# apo_board.net
KiCad netlist of a schematic drawn in EAGLE
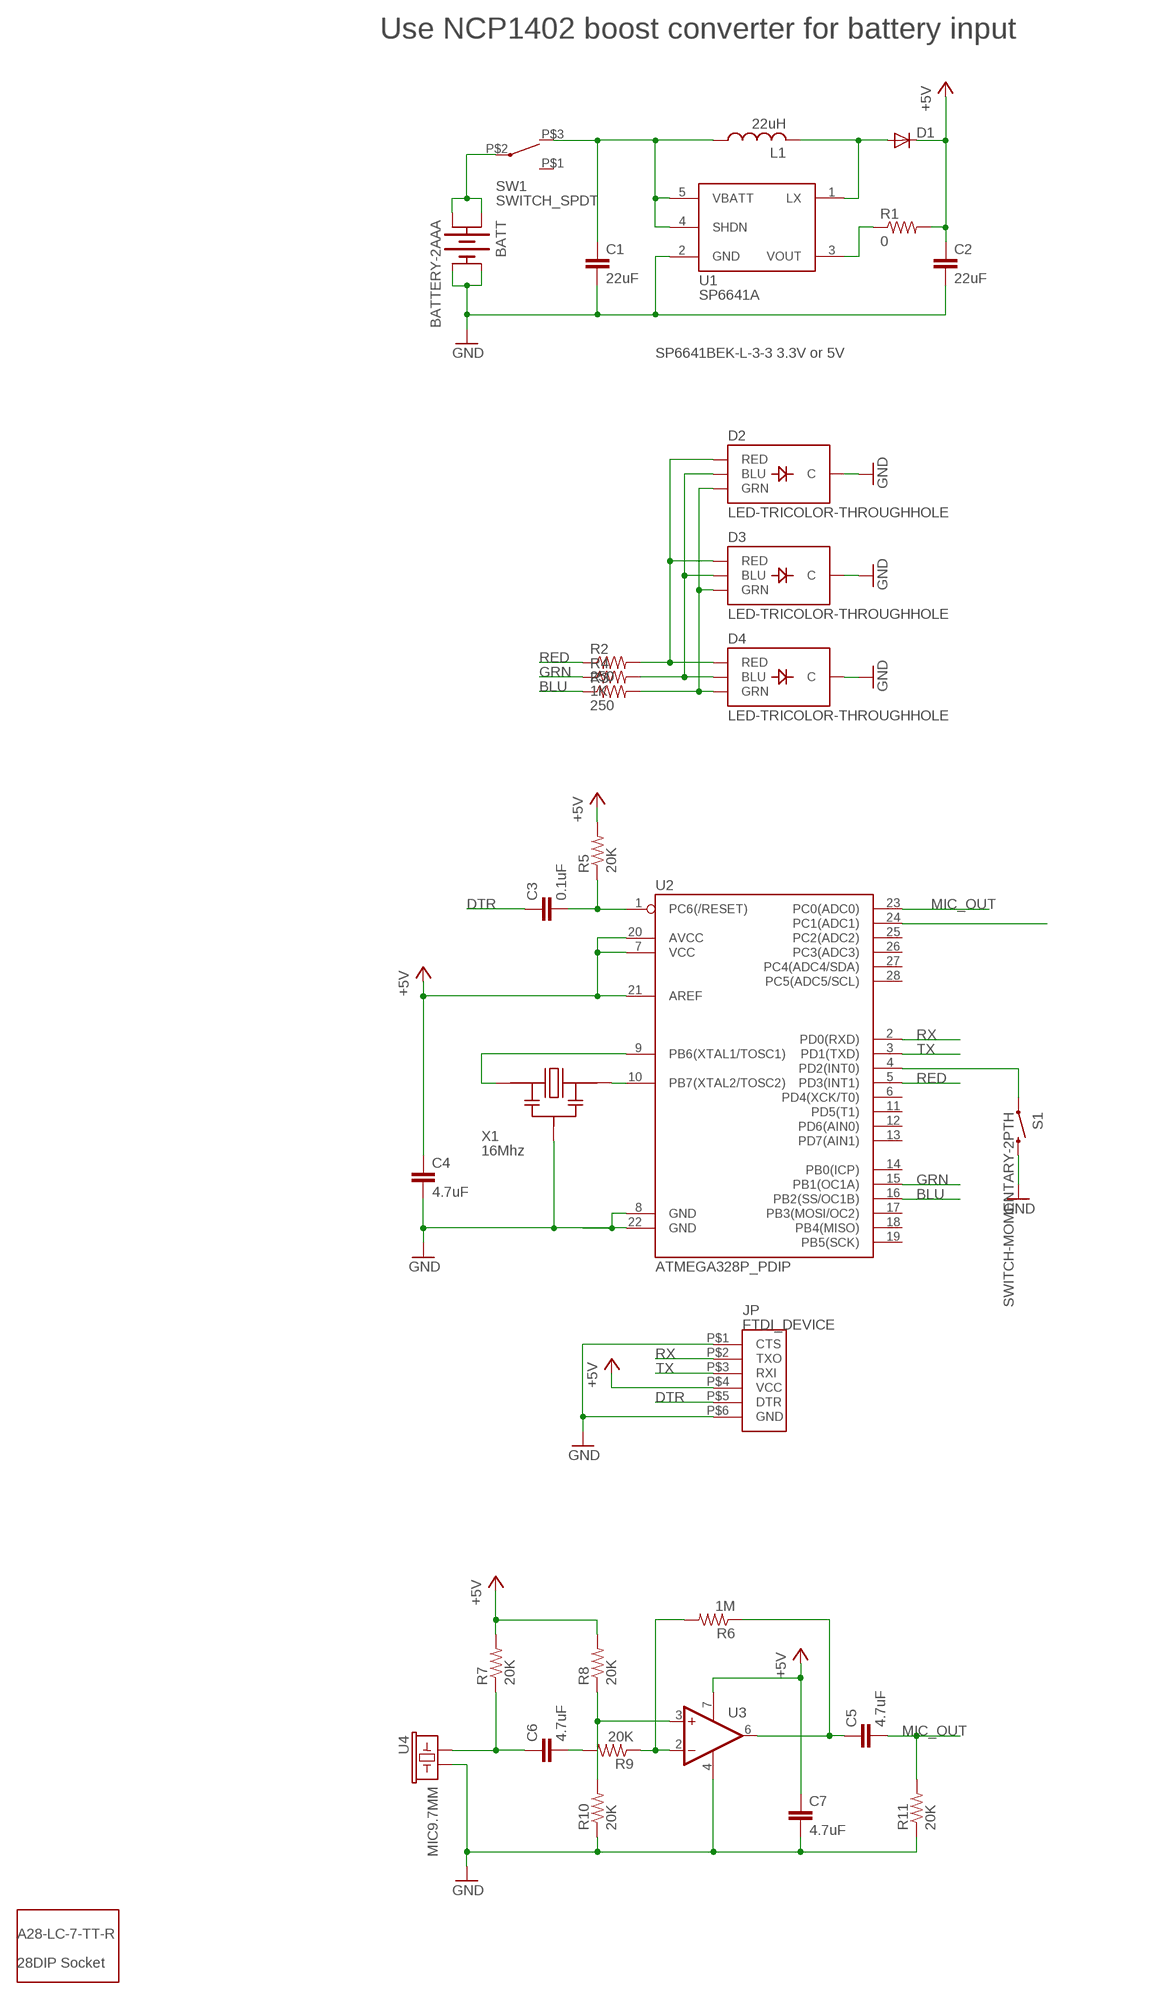
[diagram p0: schematic, sheet 1]

(export (version "E")
  (design (tool "Eeschema 10.0.6"))
  (components
    (comp (ref "BATT")
      (value "BATTERY-2AAA")
      (footprint "eagle-import:BATTERY-AAA")
      (libsource (lib "eagle-import") (part "BATTERY-2AAA"))
    )
    (comp (ref "C1")
      (value "22uF")
      (footprint "eagle-import:CAP-PTH-SMALL-KIT")
      (libsource (lib "eagle-import") (part "CAPKIT"))
    )
    (comp (ref "C2")
      (value "22uF")
      (footprint "eagle-import:CAP-PTH-SMALL-KIT")
      (libsource (lib "eagle-import") (part "CAPKIT"))
    )
    (comp (ref "C3")
      (value "0.1uF")
      (footprint "eagle-import:CAP-PTH-SMALL-KIT")
      (libsource (lib "eagle-import") (part "CAPKIT"))
    )
    (comp (ref "C4")
      (value "4.7uF")
      (footprint "eagle-import:CAP-PTH-SMALL-KIT")
      (libsource (lib "eagle-import") (part "CAPKIT"))
    )
    (comp (ref "C5")
      (value "4.7uF")
      (footprint "eagle-import:CAP-PTH-SMALL-KIT")
      (libsource (lib "eagle-import") (part "CAPKIT"))
    )
    (comp (ref "C6")
      (value "4.7uF")
      (footprint "eagle-import:CAP-PTH-SMALL-KIT")
      (libsource (lib "eagle-import") (part "CAPKIT"))
    )
    (comp (ref "C7")
      (value "4.7uF")
      (footprint "eagle-import:CAP-PTH-SMALL-KIT")
      (libsource (lib "eagle-import") (part "CAPKIT"))
    )
    (comp (ref "D1")
      (value "DIODE1N4148")
      (footprint "eagle-import:DIODE-1N4148")
      (libsource (lib "eagle-import") (part "DIODE1N4148"))
    )
    (comp (ref "D2")
      (value "LED-TRICOLOR-THROUGHHOLE")
      (footprint "eagle-import:LED-TRICOLOR-THROUGHHOLE")
      (libsource (lib "eagle-import") (part "LED-TRICOLOR-THROUGHHOLE"))
    )
    (comp (ref "D3")
      (value "LED-TRICOLOR-THROUGHHOLE")
      (footprint "eagle-import:LED-TRICOLOR-THROUGHHOLE")
      (libsource (lib "eagle-import") (part "LED-TRICOLOR-THROUGHHOLE"))
    )
    (comp (ref "D4")
      (value "LED-TRICOLOR-THROUGHHOLE")
      (footprint "eagle-import:LED-TRICOLOR-THROUGHHOLE")
      (libsource (lib "eagle-import") (part "LED-TRICOLOR-THROUGHHOLE"))
    )
    (comp (ref "JP")
      (value "FTDI_DEVICE")
      (footprint "eagle-import:FTDI_DEVICE_SIDE")
      (libsource (lib "eagle-import") (part "FTDI_DEVICE"))
    )
    (comp (ref "L1")
      (value "22uH")
      (footprint "eagle-import:INDUCTOR_AIUR-02H")
      (libsource (lib "eagle-import") (part "INDUCTORAIUR-02H"))
    )
    (comp (ref "R1")
      (value "0")
      (footprint "eagle-import:AXIAL-0.3")
      (libsource (lib "eagle-import") (part "RESISTORAXIAL-0.3"))
    )
    (comp (ref "R2")
      (value "250")
      (footprint "eagle-import:AXIAL-0.3")
      (libsource (lib "eagle-import") (part "RESISTORAXIAL-0.3"))
    )
    (comp (ref "R3")
      (value "250")
      (footprint "eagle-import:AXIAL-0.3")
      (libsource (lib "eagle-import") (part "RESISTORAXIAL-0.3"))
    )
    (comp (ref "R4")
      (value "1K")
      (footprint "eagle-import:AXIAL-0.3")
      (libsource (lib "eagle-import") (part "RESISTORAXIAL-0.3"))
    )
    (comp (ref "R5")
      (value "20K")
      (footprint "eagle-import:AXIAL-0.3")
      (libsource (lib "eagle-import") (part "RESISTORAXIAL-0.3"))
    )
    (comp (ref "R6")
      (value "1M")
      (footprint "eagle-import:AXIAL-0.3")
      (libsource (lib "eagle-import") (part "RESISTORAXIAL-0.3"))
    )
    (comp (ref "R7")
      (value "20K")
      (footprint "eagle-import:AXIAL-0.3")
      (libsource (lib "eagle-import") (part "RESISTORAXIAL-0.3"))
    )
    (comp (ref "R8")
      (value "20K")
      (footprint "eagle-import:AXIAL-0.3")
      (libsource (lib "eagle-import") (part "RESISTORAXIAL-0.3"))
    )
    (comp (ref "R9")
      (value "20K")
      (footprint "eagle-import:AXIAL-0.3")
      (libsource (lib "eagle-import") (part "RESISTORAXIAL-0.3"))
    )
    (comp (ref "R10")
      (value "20K")
      (footprint "eagle-import:AXIAL-0.3")
      (libsource (lib "eagle-import") (part "RESISTORAXIAL-0.3"))
    )
    (comp (ref "R11")
      (value "20K")
      (footprint "eagle-import:AXIAL-0.3")
      (libsource (lib "eagle-import") (part "RESISTORAXIAL-0.3"))
    )
    (comp (ref "S1")
      (value "SWITCH-MOMENTARY-2PTH")
      (footprint "eagle-import:TACTILE-PTH")
      (libsource (lib "eagle-import") (part "SWITCH-MOMENTARY-2PTH"))
    )
    (comp (ref "SW1")
      (value "SWITCH_SPDT")
      (footprint "eagle-import:SWITCH_SPDT_OS102011MA1QN1C")
      (libsource (lib "eagle-import") (part "SWITCH_SPDT"))
    )
    (comp (ref "U1")
      (value "SP6641A")
      (footprint "eagle-import:SOT23-5")
      (libsource (lib "eagle-import") (part "SP6641A"))
    )
    (comp (ref "U2")
      (value "ATMEGA328P_PDIP")
      (footprint "eagle-import:DIL28-3")
      (libsource (lib "eagle-import") (part "ATMEGA328P_PDIP"))
    )
    (comp (ref "U3")
      (value "1AMP_P7+4N")
      (footprint "eagle-import:DIL08")
      (libsource (lib "eagle-import") (part "1AMP_P7+4N"))
    )
    (comp (ref "U4")
      (value "MIC9.7MM")
      (footprint "eagle-import:MIC-9.7MM")
      (libsource (lib "eagle-import") (part "MIC9.7MM"))
    )
    (comp (ref "X1")
      (value "16Mhz")
      (footprint "eagle-import:CERAMIC_RESONATOR_ZTT")
      (libsource (lib "eagle-import") (part "CERAMIC_RESONATOR"))
    )
  )
  (nets
    (net (code "1") (name "+5V") (class "Default")
      (node (ref "C2") (pin "1") (pinfunction "1_1") (pintype "passive"))
      (node (ref "C4") (pin "1") (pinfunction "1_1") (pintype "passive"))
      (node (ref "C7") (pin "1") (pinfunction "1_1") (pintype "passive"))
      (node (ref "D1") (pin "C") (pinfunction "C_C") (pintype "passive"))
      (node (ref "JP") (pin "P$4") (pinfunction "VCC_P$4") (pintype "bidirectional"))
      (node (ref "R1") (pin "P$2") (pinfunction "2_P$2") (pintype "passive"))
      (node (ref "R5") (pin "P$2") (pinfunction "2_P$2") (pintype "passive"))
      (node (ref "R7") (pin "P$2") (pinfunction "2_P$2") (pintype "passive"))
      (node (ref "R8") (pin "P$2") (pinfunction "2_P$2") (pintype "passive"))
      (node (ref "U2") (pin "20") (pinfunction "AVCC_20") (pintype "bidirectional"))
      (node (ref "U2") (pin "21") (pinfunction "AREF_21") (pintype "bidirectional"))
      (node (ref "U2") (pin "7") (pinfunction "VCC_7") (pintype "bidirectional"))
      (node (ref "U3") (pin "7") (pinfunction "V+_7") (pintype "power_in"))
    )
    (net (code "2") (name "/BLU") (class "Default")
      (node (ref "R3") (pin "P$1") (pinfunction "1_P$1") (pintype "passive"))
      (node (ref "U2") (pin "16") (pinfunction "PB2(SS/OC1B)_16") (pintype "bidirectional"))
    )
    (net (code "3") (name "/DTR") (class "Default")
      (node (ref "C3") (pin "1") (pinfunction "1_1") (pintype "passive"))
      (node (ref "JP") (pin "P$5") (pinfunction "DTR_P$5") (pintype "bidirectional"))
    )
    (net (code "4") (name "/GRN") (class "Default")
      (node (ref "R4") (pin "P$1") (pinfunction "1_P$1") (pintype "passive"))
      (node (ref "U2") (pin "15") (pinfunction "PB1(OC1A)_15") (pintype "bidirectional"))
    )
    (net (code "5") (name "/MIC_OUT") (class "Default")
      (node (ref "C5") (pin "2") (pinfunction "2_2") (pintype "passive"))
      (node (ref "R11") (pin "P$2") (pinfunction "2_P$2") (pintype "passive"))
      (node (ref "U2") (pin "23") (pinfunction "PC0(ADC0)_23") (pintype "bidirectional"))
    )
    (net (code "6") (name "/RED") (class "Default")
      (node (ref "R2") (pin "P$1") (pinfunction "1_P$1") (pintype "passive"))
      (node (ref "U2") (pin "5") (pinfunction "PD3(INT1)_5") (pintype "bidirectional"))
    )
    (net (code "7") (name "/RX") (class "Default")
      (node (ref "JP") (pin "P$2") (pinfunction "TXO_P$2") (pintype "bidirectional"))
      (node (ref "U2") (pin "2") (pinfunction "PD0(RXD)_2") (pintype "bidirectional"))
    )
    (net (code "8") (name "/TX") (class "Default")
      (node (ref "JP") (pin "P$3") (pinfunction "RXI_P$3") (pintype "bidirectional"))
      (node (ref "U2") (pin "3") (pinfunction "PD1(TXD)_3") (pintype "bidirectional"))
    )
    (net (code "9") (name "GND") (class "Default")
      (node (ref "BATT") (pin "GND@1") (pinfunction "-1_GND@1") (pintype "power_in"))
      (node (ref "BATT") (pin "GND@2") (pinfunction "-2_GND@2") (pintype "power_in"))
      (node (ref "C1") (pin "2") (pinfunction "2_2") (pintype "passive"))
      (node (ref "C2") (pin "2") (pinfunction "2_2") (pintype "passive"))
      (node (ref "C4") (pin "2") (pinfunction "2_2") (pintype "passive"))
      (node (ref "C7") (pin "2") (pinfunction "2_2") (pintype "passive"))
      (node (ref "D2") (pin "GND") (pinfunction "C_GND") (pintype "bidirectional"))
      (node (ref "D3") (pin "GND") (pinfunction "C_GND") (pintype "bidirectional"))
      (node (ref "D4") (pin "GND") (pinfunction "C_GND") (pintype "bidirectional"))
      (node (ref "JP") (pin "P$1") (pinfunction "CTS_P$1") (pintype "bidirectional"))
      (node (ref "JP") (pin "P$6") (pinfunction "GND_P$6") (pintype "bidirectional"))
      (node (ref "R10") (pin "P$1") (pinfunction "1_P$1") (pintype "passive"))
      (node (ref "R11") (pin "P$1") (pinfunction "1_P$1") (pintype "passive"))
      (node (ref "S1") (pin "3") (pinfunction "2_3") (pintype "passive"))
      (node (ref "U1") (pin "2") (pinfunction "GND_2") (pintype "bidirectional"))
      (node (ref "U2") (pin "22") (pinfunction "GND_22") (pintype "bidirectional"))
      (node (ref "U2") (pin "8") (pinfunction "GND_8") (pintype "bidirectional"))
      (node (ref "U3") (pin "4") (pinfunction "V-_4") (pintype "power_in"))
      (node (ref "U4") (pin "2") (pinfunction "2_2") (pintype "passive"))
      (node (ref "X1") (pin "P$2") (pinfunction "P$2_P$2") (pintype "bidirectional"))
    )
    (net (code "10") (name "Net-(BATT-+1)") (class "Default")
      (node (ref "BATT") (pin "PWR@1") (pinfunction "+1_PWR@1") (pintype "power_in"))
      (node (ref "BATT") (pin "PWR@2") (pinfunction "+2_PWR@2") (pintype "power_in"))
      (node (ref "SW1") (pin "P$2") (pinfunction "COMMON_P$2") (pintype "passive"))
    )
    (net (code "11") (name "Net-(L1-1)") (class "Default")
      (node (ref "C1") (pin "1") (pinfunction "1_1") (pintype "passive"))
      (node (ref "L1") (pin "P$1") (pinfunction "1_P$1") (pintype "passive"))
      (node (ref "SW1") (pin "P$3") (pinfunction "3_P$3") (pintype "passive"))
      (node (ref "U1") (pin "4") (pinfunction "SHDN_4") (pintype "bidirectional"))
      (node (ref "U1") (pin "5") (pinfunction "VBATT_5") (pintype "bidirectional"))
    )
    (net (code "12") (name "Net-(L1-2)") (class "Default")
      (node (ref "D1") (pin "A") (pinfunction "A_A") (pintype "passive"))
      (node (ref "L1") (pin "P$2") (pinfunction "2_P$2") (pintype "passive"))
      (node (ref "U1") (pin "1") (pinfunction "LX_1") (pintype "bidirectional"))
    )
    (net (code "13") (name "Net-(R1-1)") (class "Default")
      (node (ref "R1") (pin "P$1") (pinfunction "1_P$1") (pintype "passive"))
      (node (ref "U1") (pin "3") (pinfunction "VOUT_3") (pintype "bidirectional"))
    )
    (net (code "14") (name "Net-(R2-2)") (class "Default")
      (node (ref "D2") (pin "RED") (pinfunction "RED_RED") (pintype "bidirectional"))
      (node (ref "D3") (pin "RED") (pinfunction "RED_RED") (pintype "bidirectional"))
      (node (ref "D4") (pin "RED") (pinfunction "RED_RED") (pintype "bidirectional"))
      (node (ref "R2") (pin "P$2") (pinfunction "2_P$2") (pintype "passive"))
    )
    (net (code "15") (name "Net-(R3-2)") (class "Default")
      (node (ref "D2") (pin "GRN") (pinfunction "GRN_GRN") (pintype "bidirectional"))
      (node (ref "D3") (pin "GRN") (pinfunction "GRN_GRN") (pintype "bidirectional"))
      (node (ref "D4") (pin "GRN") (pinfunction "GRN_GRN") (pintype "bidirectional"))
      (node (ref "R3") (pin "P$2") (pinfunction "2_P$2") (pintype "passive"))
    )
    (net (code "16") (name "Net-(R4-2)") (class "Default")
      (node (ref "D2") (pin "BLU") (pinfunction "BLU_BLU") (pintype "bidirectional"))
      (node (ref "D3") (pin "BLU") (pinfunction "BLU_BLU") (pintype "bidirectional"))
      (node (ref "D4") (pin "BLU") (pinfunction "BLU_BLU") (pintype "bidirectional"))
      (node (ref "R4") (pin "P$2") (pinfunction "2_P$2") (pintype "passive"))
    )
    (net (code "17") (name "Net-(R5-1)") (class "Default")
      (node (ref "C3") (pin "2") (pinfunction "2_2") (pintype "passive"))
      (node (ref "R5") (pin "P$1") (pinfunction "1_P$1") (pintype "passive"))
      (node (ref "U2") (pin "1") (pinfunction "PC6(/RESET)_1") (pintype "bidirectional"))
    )
    (net (code "18") (name "Net-(R6-1)") (class "Default")
      (node (ref "C5") (pin "1") (pinfunction "1_1") (pintype "passive"))
      (node (ref "R6") (pin "P$1") (pinfunction "1_P$1") (pintype "passive"))
      (node (ref "U3") (pin "6") (pinfunction "OUT_6") (pintype "output"))
    )
    (net (code "19") (name "Net-(R6-2)") (class "Default")
      (node (ref "R6") (pin "P$2") (pinfunction "2_P$2") (pintype "passive"))
      (node (ref "R9") (pin "P$1") (pinfunction "1_P$1") (pintype "passive"))
      (node (ref "U3") (pin "2") (pinfunction "-IN_2") (pintype "input"))
    )
    (net (code "20") (name "Net-(R7-1)") (class "Default")
      (node (ref "C6") (pin "1") (pinfunction "1_1") (pintype "passive"))
      (node (ref "R7") (pin "P$1") (pinfunction "1_P$1") (pintype "passive"))
      (node (ref "U4") (pin "1") (pinfunction "1_1") (pintype "passive"))
    )
    (net (code "21") (name "Net-(R9-2)") (class "Default")
      (node (ref "C6") (pin "2") (pinfunction "2_2") (pintype "passive"))
      (node (ref "R9") (pin "P$2") (pinfunction "2_P$2") (pintype "passive"))
    )
    (net (code "22") (name "Net-(R10-2)") (class "Default")
      (node (ref "R10") (pin "P$2") (pinfunction "2_P$2") (pintype "passive"))
      (node (ref "R8") (pin "P$1") (pinfunction "1_P$1") (pintype "passive"))
      (node (ref "U3") (pin "3") (pinfunction "+IN_3") (pintype "input"))
    )
    (net (code "23") (name "Net-(U2-PB6(XTAL1{slash}TOSC1))") (class "Default")
      (node (ref "U2") (pin "9") (pinfunction "PB6(XTAL1/TOSC1)_9") (pintype "bidirectional"))
      (node (ref "X1") (pin "P$1") (pinfunction "P$1_P$1") (pintype "bidirectional"))
    )
    (net (code "24") (name "Net-(U2-PB7(XTAL2{slash}TOSC2))") (class "Default")
      (node (ref "U2") (pin "10") (pinfunction "PB7(XTAL2/TOSC2)_10") (pintype "bidirectional"))
      (node (ref "X1") (pin "P$3") (pinfunction "P$3_P$3") (pintype "bidirectional"))
    )
    (net (code "25") (name "Net-(U2-PD2(INT0))") (class "Default")
      (node (ref "S1") (pin "1") (pinfunction "1_1") (pintype "passive"))
      (node (ref "U2") (pin "4") (pinfunction "PD2(INT0)_4") (pintype "bidirectional"))
    )
    (net (code "26") (name "unconnected-(SW1-2-PadP$1)") (class "Default")
      (node (ref "SW1") (pin "P$1") (pinfunction "2_P$1") (pintype "passive"))
    )
    (net (code "27") (name "unconnected-(U2-PB0(ICP)-Pad14)") (class "Default")
      (node (ref "U2") (pin "14") (pinfunction "PB0(ICP)_14") (pintype "bidirectional"))
    )
    (net (code "28") (name "unconnected-(U2-PB3(MOSI{slash}OC2)-Pad17)") (class "Default")
      (node (ref "U2") (pin "17") (pinfunction "PB3(MOSI/OC2)_17") (pintype "bidirectional"))
    )
    (net (code "29") (name "unconnected-(U2-PB4(MISO)-Pad18)") (class "Default")
      (node (ref "U2") (pin "18") (pinfunction "PB4(MISO)_18") (pintype "bidirectional"))
    )
    (net (code "30") (name "unconnected-(U2-PB5(SCK)-Pad19)") (class "Default")
      (node (ref "U2") (pin "19") (pinfunction "PB5(SCK)_19") (pintype "bidirectional"))
    )
    (net (code "31") (name "unconnected-(U2-PC1(ADC1)-Pad24)") (class "Default")
      (node (ref "U2") (pin "24") (pinfunction "PC1(ADC1)_24") (pintype "bidirectional"))
    )
    (net (code "32") (name "unconnected-(U2-PC2(ADC2)-Pad25)") (class "Default")
      (node (ref "U2") (pin "25") (pinfunction "PC2(ADC2)_25") (pintype "bidirectional"))
    )
    (net (code "33") (name "unconnected-(U2-PC3(ADC3)-Pad26)") (class "Default")
      (node (ref "U2") (pin "26") (pinfunction "PC3(ADC3)_26") (pintype "bidirectional"))
    )
    (net (code "34") (name "unconnected-(U2-PC4(ADC4{slash}SDA)-Pad27)") (class "Default")
      (node (ref "U2") (pin "27") (pinfunction "PC4(ADC4/SDA)_27") (pintype "bidirectional"))
    )
    (net (code "35") (name "unconnected-(U2-PC5(ADC5{slash}SCL)-Pad28)") (class "Default")
      (node (ref "U2") (pin "28") (pinfunction "PC5(ADC5/SCL)_28") (pintype "bidirectional"))
    )
    (net (code "36") (name "unconnected-(U2-PD4(XCK{slash}T0)-Pad6)") (class "Default")
      (node (ref "U2") (pin "6") (pinfunction "PD4(XCK/T0)_6") (pintype "bidirectional"))
    )
    (net (code "37") (name "unconnected-(U2-PD5(T1)-Pad11)") (class "Default")
      (node (ref "U2") (pin "11") (pinfunction "PD5(T1)_11") (pintype "bidirectional"))
    )
    (net (code "38") (name "unconnected-(U2-PD6(AIN0)-Pad12)") (class "Default")
      (node (ref "U2") (pin "12") (pinfunction "PD6(AIN0)_12") (pintype "bidirectional"))
    )
    (net (code "39") (name "unconnected-(U2-PD7(AIN1)-Pad13)") (class "Default")
      (node (ref "U2") (pin "13") (pinfunction "PD7(AIN1)_13") (pintype "bidirectional"))
    )
  )
)
